# Sensor_hall.net
KiCad netlist of a schematic drawn in EAGLE
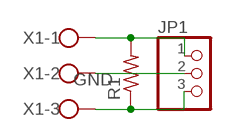
[diagram p0: schematic, sheet 1]

(export (version "E")
  (design (tool "Eeschema 10.0.6"))
  (components
    (comp (ref "JP1")
      (value "PINHD-1X3")
      (footprint "eagle-import:1X03")
      (libsource (lib "eagle-import") (part "PINHD-1X3"))
    )
    (comp (ref "R1")
      (value "R-US_0411/15")
      (footprint "eagle-import:0411_15")
      (libsource (lib "eagle-import") (part "R-US_0411/15"))
    )
    (comp (ref "X1")
      (value "W237-103")
      (footprint "eagle-import:W237-103")
      (fields (field (name "MPN") "237-103"))
      (libsource (lib "eagle-import") (part "W237-103"))
    )
  )
  (nets
    (net (code "1") (name "/GND") (class "Default")
      (node (ref "JP1") (pin "2") (pinfunction "2_2") (pintype "passive"))
      (node (ref "X1") (pin "2") (pinfunction "KL_2") (pintype "passive"))
    )
    (net (code "2") (name "Net-(X1A-KL)") (class "Default")
      (node (ref "JP1") (pin "1") (pinfunction "1_1") (pintype "passive"))
      (node (ref "R1") (pin "2") (pinfunction "2_2") (pintype "passive"))
      (node (ref "X1") (pin "1") (pinfunction "KL_1") (pintype "passive"))
    )
    (net (code "3") (name "Net-(X1C-KL)") (class "Default")
      (node (ref "JP1") (pin "3") (pinfunction "3_3") (pintype "passive"))
      (node (ref "R1") (pin "1") (pinfunction "1_1") (pintype "passive"))
      (node (ref "X1") (pin "3") (pinfunction "KL_3") (pintype "passive"))
    )
  )
)
